# igvc-neopixel.net
KiCad netlist of a schematic drawn in EAGLE
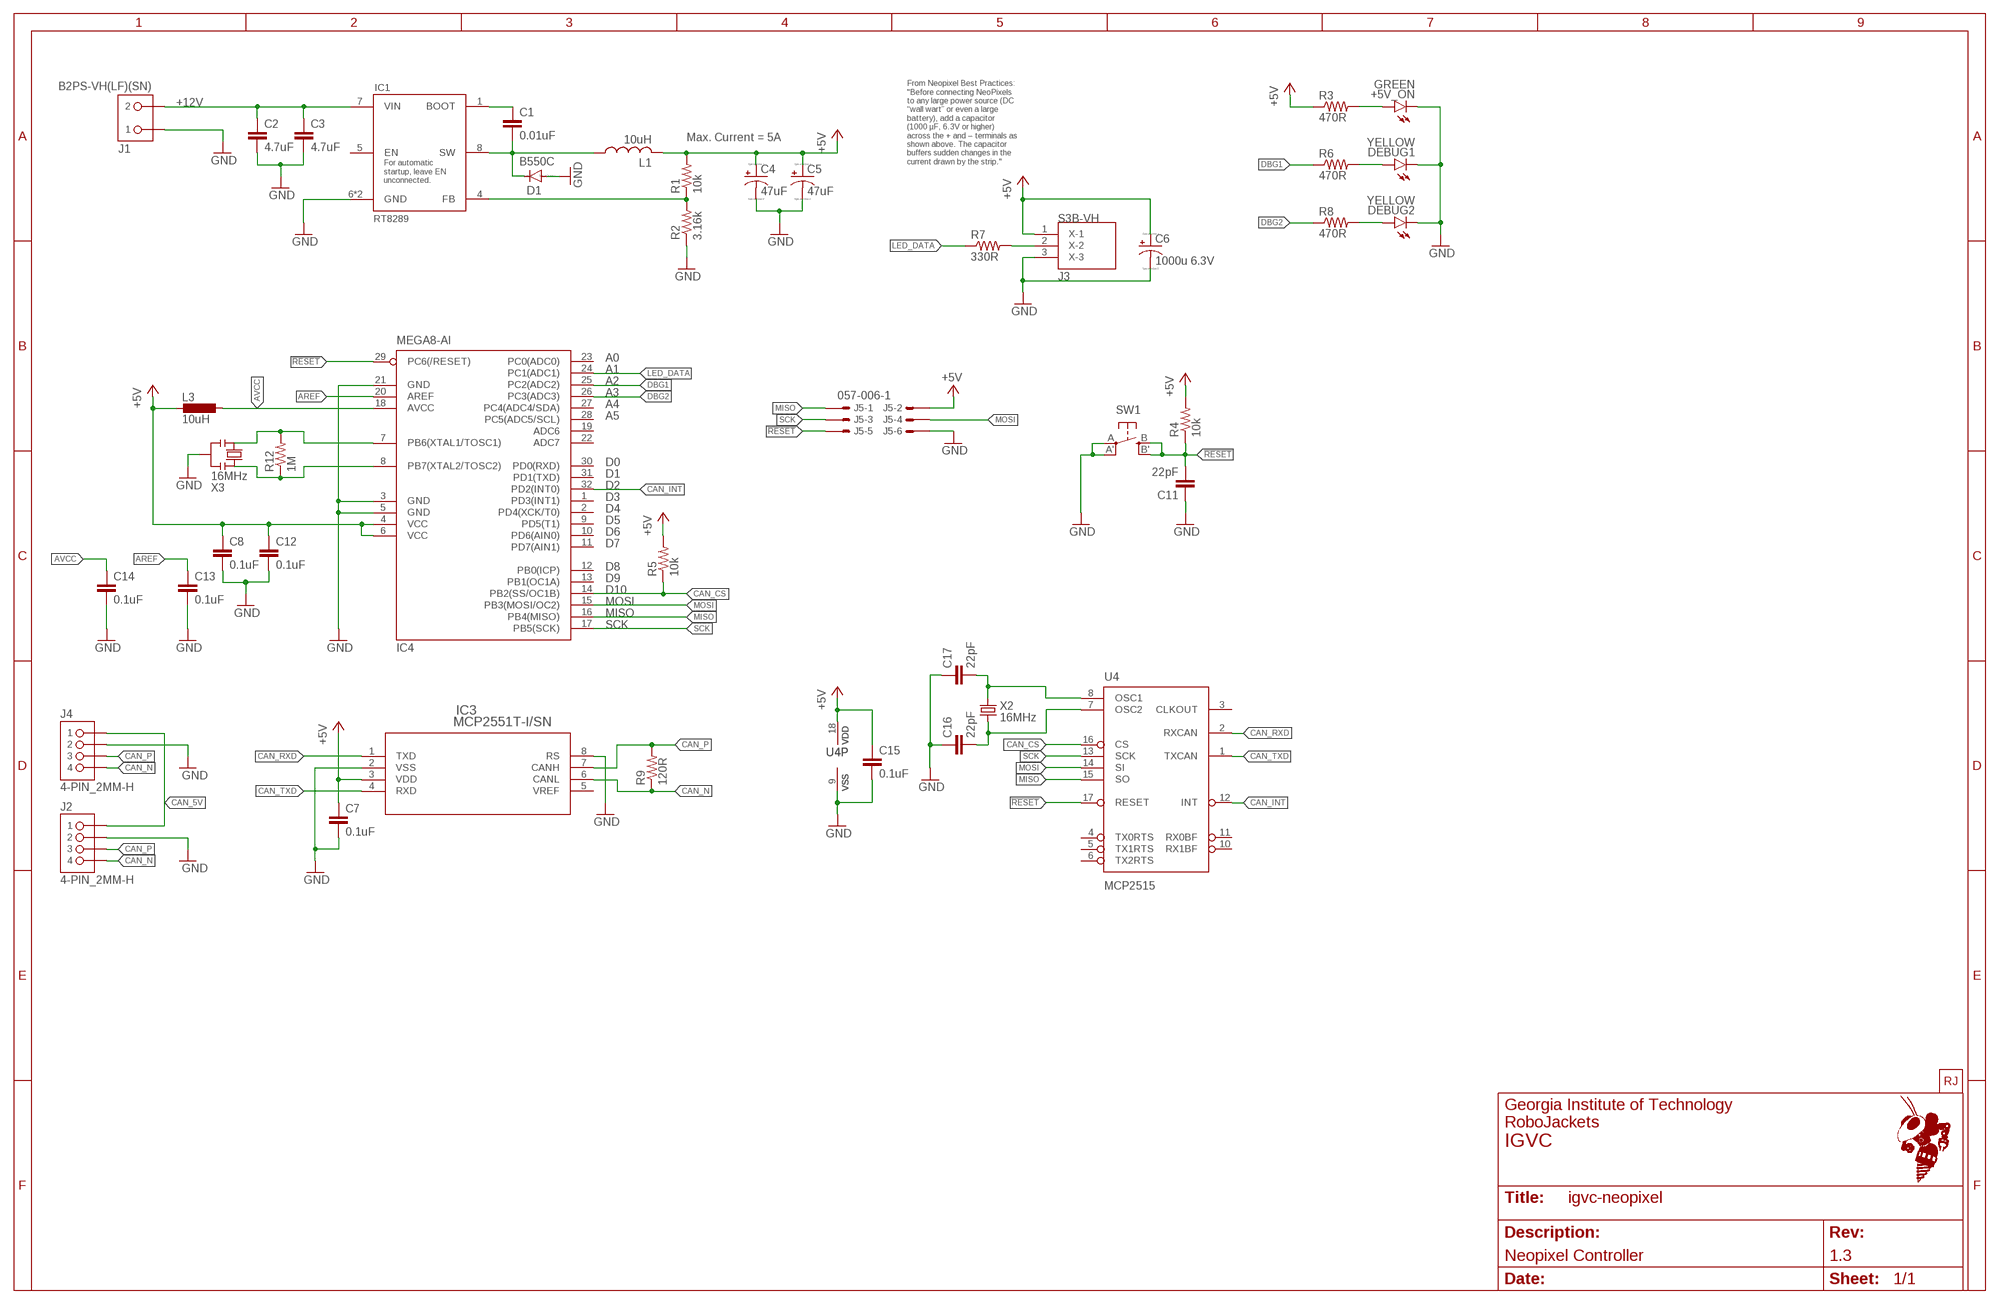
[diagram p0: schematic, sheet 1]

(export (version "E")
  (design (tool "Eeschema 10.0.6"))
  (components
    (comp (ref "+5V_ON")
      (value "GREEN")
      (footprint "eagle-import:CHIP-LED0805")
      (libsource (lib "eagle-import") (part "LEDCHIP-LED0805"))
    )
    (comp (ref "C1")
      (value "0.01uF")
      (footprint "eagle-import:C0603")
      (libsource (lib "eagle-import") (part "resistor_348_C-EUC0603"))
    )
    (comp (ref "C2")
      (value "4.7uF")
      (footprint "eagle-import:C1206")
      (libsource (lib "eagle-import") (part "resistor_348_C-EUC1206"))
    )
    (comp (ref "C3")
      (value "4.7uF")
      (footprint "eagle-import:C1206")
      (libsource (lib "eagle-import") (part "resistor_348_C-EUC1206"))
    )
    (comp (ref "C4")
      (value "47uF")
      (footprint "eagle-import:E5-10,5")
      (libsource (lib "eagle-import") (part "CPOL-USE5-10.5"))
    )
    (comp (ref "C5")
      (value "47uF")
      (footprint "eagle-import:E5-10,5")
      (libsource (lib "eagle-import") (part "CPOL-USE5-10.5"))
    )
    (comp (ref "C6")
      (value "1000u 6.3V")
      (footprint "eagle-import:E5-10,5")
      (libsource (lib "eagle-import") (part "CPOL-USE5-10.5"))
    )
    (comp (ref "C7")
      (value "0.1uF")
      (footprint "eagle-import:C0603")
      (libsource (lib "eagle-import") (part "C-EUC0603"))
    )
    (comp (ref "C8")
      (value "0.1uF")
      (footprint "eagle-import:C0603")
      (libsource (lib "eagle-import") (part "resistor_348_C-EUC0603"))
    )
    (comp (ref "C11")
      (value "22pF")
      (footprint "eagle-import:C0603")
      (libsource (lib "eagle-import") (part "resistor_348_C-EUC0603"))
    )
    (comp (ref "C12")
      (value "0.1uF")
      (footprint "eagle-import:C0603")
      (libsource (lib "eagle-import") (part "resistor_348_C-EUC0603"))
    )
    (comp (ref "C13")
      (value "0.1uF")
      (footprint "eagle-import:C0603")
      (libsource (lib "eagle-import") (part "resistor_348_C-EUC0603"))
    )
    (comp (ref "C14")
      (value "0.1uF")
      (footprint "eagle-import:C0603")
      (libsource (lib "eagle-import") (part "resistor_348_C-EUC0603"))
    )
    (comp (ref "C15")
      (value "0.1uF")
      (footprint "eagle-import:C0603")
      (libsource (lib "eagle-import") (part "C-EUC0603"))
    )
    (comp (ref "C16")
      (value "22pF")
      (footprint "eagle-import:C0603")
      (libsource (lib "eagle-import") (part "resistor_348_C-EUC0603"))
    )
    (comp (ref "C17")
      (value "22pF")
      (footprint "eagle-import:C0603")
      (libsource (lib "eagle-import") (part "resistor_348_C-EUC0603"))
    )
    (comp (ref "D1")
      (value "B550C")
      (footprint "eagle-import:SMC")
      (libsource (lib "eagle-import") (part "DIODE-SMC"))
    )
    (comp (ref "DEBUG1")
      (value "YELLOW")
      (footprint "eagle-import:CHIP-LED0805")
      (libsource (lib "eagle-import") (part "LEDCHIP-LED0805"))
    )
    (comp (ref "DEBUG2")
      (value "YELLOW")
      (footprint "eagle-import:CHIP-LED0805")
      (libsource (lib "eagle-import") (part "LEDCHIP-LED0805"))
    )
    (comp (ref "IC1")
      (value "RT8289")
      (footprint "eagle-import:SOIC8_EP")
      (libsource (lib "eagle-import") (part "RT8289"))
    )
    (comp (ref "IC3")
      (value "MCP2551T-I/SN")
      (footprint "eagle-import:SOIC8-N_MC")
      (fields (field (name "MANUFACTURER_PART_NUMBER") "MCP2551TISN"))
      (libsource (lib "eagle-import") (part "MCP2551T-I/SN"))
    )
    (comp (ref "IC4")
      (value "MEGA8-AI")
      (footprint "eagle-import:TQFP32-08")
      (fields (field (name "MPN") "ATMEGA8-16AU"))
      (libsource (lib "eagle-import") (part "MEGA8-AI"))
    )
    (comp (ref "J1")
      (value "B2PS-VH(LF)(SN)")
      (footprint "eagle-import:B2PS-CENTERED")
      (libsource (lib "eagle-import") (part "B2P?-VH(LF)(SN)S"))
    )
    (comp (ref "J2")
      (value "4-PIN_2MM-H")
      (footprint "eagle-import:2MM-4-H")
      (fields (field (name "MPN") "0353630460"))
      (libsource (lib "eagle-import") (part "4-PIN_2MM-H"))
    )
    (comp (ref "J3")
      (value "S3B-VH")
      (footprint "eagle-import:S3B-VH")
      (libsource (lib "eagle-import") (part "S3B-VH"))
    )
    (comp (ref "J4")
      (value "4-PIN_2MM-H")
      (footprint "eagle-import:2MM-4-H")
      (fields (field (name "MPN") "0353630460"))
      (libsource (lib "eagle-import") (part "4-PIN_2MM-H"))
    )
    (comp (ref "J5")
      (value "057-006-1")
      (footprint "eagle-import:057-006-1")
      (fields (field (name "DIGIKEY") "3M15451-ND"))
      (libsource (lib "eagle-import") (part "057-006-1"))
    )
    (comp (ref "L1")
      (value "10uH")
      (footprint "eagle-import:SRR1208")
      (libsource (lib "eagle-import") (part "SRR1208"))
    )
    (comp (ref "L3")
      (value "10uH")
      (footprint "eagle-import:0805")
      (libsource (lib "eagle-import") (part "L-0805"))
    )
    (comp (ref "R1")
      (value "10k")
      (footprint "eagle-import:R0603")
      (libsource (lib "eagle-import") (part "resistor_348_R-US_R0603"))
    )
    (comp (ref "R2")
      (value "3.16k")
      (footprint "eagle-import:R0603")
      (libsource (lib "eagle-import") (part "resistor_348_R-US_R0603"))
    )
    (comp (ref "R3")
      (value "470R")
      (footprint "eagle-import:R0603")
      (libsource (lib "eagle-import") (part "resistor_348_R-US_R0603"))
    )
    (comp (ref "R4")
      (value "10k")
      (footprint "eagle-import:R0603")
      (libsource (lib "eagle-import") (part "resistor_348_R-US_R0603"))
    )
    (comp (ref "R5")
      (value "10k")
      (footprint "eagle-import:R0603")
      (libsource (lib "eagle-import") (part "R-US_R0603"))
    )
    (comp (ref "R6")
      (value "470R")
      (footprint "eagle-import:R0603")
      (libsource (lib "eagle-import") (part "resistor_348_R-US_R0603"))
    )
    (comp (ref "R7")
      (value "330R")
      (footprint "eagle-import:R0603")
      (libsource (lib "eagle-import") (part "R-US_R0603"))
    )
    (comp (ref "R8")
      (value "470R")
      (footprint "eagle-import:R0603")
      (libsource (lib "eagle-import") (part "resistor_348_R-US_R0603"))
    )
    (comp (ref "R9")
      (value "120R")
      (footprint "eagle-import:R0603")
      (libsource (lib "eagle-import") (part "R-US_R0603"))
    )
    (comp (ref "R12")
      (value "1M")
      (footprint "eagle-import:R0603")
      (libsource (lib "eagle-import") (part "resistor_348_R-US_R0603"))
    )
    (comp (ref "SW1")
      (value "SPST_TACT-EVQQ2")
      (footprint "eagle-import:EVQ-Q2")
      (libsource (lib "eagle-import") (part "SPST_TACT-EVQQ2"))
    )
    (comp (ref "U$1")
      (value "ROBOBUZZ0.6X")
      (footprint "eagle-import:ROBOBUZZ_0.6X")
      (libsource (lib "eagle-import") (part "ROBOBUZZ0.6X"))
    )
    (comp (ref "U4")
      (value "MCP2515")
      (footprint "eagle-import:SO-18W")
      (libsource (lib "eagle-import") (part "MCP2510SO"))
    )
    (comp (ref "X2")
      (value "16MHz")
      (footprint "eagle-import:CRYSTAL-SMD-5X3")
      (libsource (lib "eagle-import") (part "CRYSTAL5X3"))
    )
    (comp (ref "X3")
      (value "16MHz")
      (footprint "eagle-import:RESONATOR")
      (fields (field (name "PART_NUMBER") "CSTCE16M0V53-R0"))
      (libsource (lib "eagle-import") (part "OSC_CSTCE16M0V53-R0"))
    )
  )
  (nets
    (net (code "1") (name "+5V") (class "Default")
      (node (ref "C12") (pin "1") (pinfunction "1_1") (pintype "passive"))
      (node (ref "C15") (pin "1") (pinfunction "1_1") (pintype "passive"))
      (node (ref "C4") (pin "+") (pinfunction "+_+") (pintype "passive"))
      (node (ref "C5") (pin "+") (pinfunction "+_+") (pintype "passive"))
      (node (ref "C6") (pin "+") (pinfunction "+_+") (pintype "passive"))
      (node (ref "C7") (pin "1") (pinfunction "1_1") (pintype "passive"))
      (node (ref "C8") (pin "1") (pinfunction "1_1") (pintype "passive"))
      (node (ref "IC3") (pin "3") (pinfunction "VDD_3") (pintype "passive"))
      (node (ref "IC4") (pin "4") (pinfunction "VCC_4") (pintype "power_in"))
      (node (ref "IC4") (pin "6") (pinfunction "VCC_6") (pintype "power_in"))
      (node (ref "J3") (pin "1") (pinfunction "X-1_1") (pintype "bidirectional"))
      (node (ref "J5") (pin "2") (pinfunction "S_2") (pintype "passive"))
      (node (ref "L1") (pin "2") (pinfunction "2_2") (pintype "passive"))
      (node (ref "L3") (pin "2") (pinfunction "2_2") (pintype "passive"))
      (node (ref "R1") (pin "2") (pinfunction "2_2") (pintype "passive"))
      (node (ref "R3") (pin "1") (pinfunction "1_1") (pintype "passive"))
      (node (ref "R4") (pin "2") (pinfunction "2_2") (pintype "passive"))
      (node (ref "R5") (pin "2") (pinfunction "2_2") (pintype "passive"))
      (node (ref "U4") (pin "18") (pinfunction "VDD_18") (pintype "power_in"))
    )
    (net (code "2") (name "/+12V") (class "Default")
      (node (ref "C2") (pin "1") (pinfunction "1_1") (pintype "passive"))
      (node (ref "C3") (pin "1") (pinfunction "1_1") (pintype "passive"))
      (node (ref "IC1") (pin "7") (pinfunction "VIN_7") (pintype "power_in"))
      (node (ref "J1") (pin "2") (pinfunction "2_2") (pintype "bidirectional"))
    )
    (net (code "3") (name "/~{RESET}") (class "Default")
      (node (ref "C11") (pin "2") (pinfunction "2_2") (pintype "passive"))
      (node (ref "IC4") (pin "29") (pinfunction "PC6(/RESET)_29") (pintype "bidirectional"))
      (node (ref "J5") (pin "5") (pinfunction "S_5") (pintype "passive"))
      (node (ref "R4") (pin "1") (pinfunction "1_1") (pintype "passive"))
      (node (ref "SW1") (pin "B") (pinfunction "S_B") (pintype "passive"))
      (node (ref "SW1") (pin "B'") (pinfunction "S1_B'") (pintype "passive"))
      (node (ref "U4") (pin "17") (pinfunction "RESET_17") (pintype "input"))
    )
    (net (code "4") (name "AREF") (class "Default")
      (node (ref "C13") (pin "1") (pinfunction "1_1") (pintype "passive"))
      (node (ref "IC4") (pin "20") (pinfunction "AREF_20") (pintype "passive"))
    )
    (net (code "5") (name "AVCC") (class "Default")
      (node (ref "C14") (pin "1") (pinfunction "1_1") (pintype "passive"))
      (node (ref "IC4") (pin "18") (pinfunction "AVCC_18") (pintype "power_in"))
      (node (ref "L3") (pin "1") (pinfunction "1_1") (pintype "passive"))
    )
    (net (code "6") (name "CAN_5V") (class "Default")
      (node (ref "J2") (pin "1") (pinfunction "1_1") (pintype "passive"))
      (node (ref "J4") (pin "1") (pinfunction "1_1") (pintype "passive"))
    )
    (net (code "7") (name "CAN_CS") (class "Default")
      (node (ref "IC4") (pin "14") (pinfunction "PB2(SS/OC1B)_14") (pintype "bidirectional"))
      (node (ref "R5") (pin "1") (pinfunction "1_1") (pintype "passive"))
      (node (ref "U4") (pin "16") (pinfunction "CS_16") (pintype "input"))
    )
    (net (code "8") (name "CAN_INT") (class "Default")
      (node (ref "IC4") (pin "32") (pinfunction "PD2(INT0)_32") (pintype "bidirectional"))
      (node (ref "U4") (pin "12") (pinfunction "INT_12") (pintype "output"))
    )
    (net (code "9") (name "CAN_N") (class "Default")
      (node (ref "IC3") (pin "6") (pinfunction "CANL_6") (pintype "passive"))
      (node (ref "J2") (pin "4") (pinfunction "4_4") (pintype "passive"))
      (node (ref "J4") (pin "4") (pinfunction "4_4") (pintype "passive"))
      (node (ref "R9") (pin "1") (pinfunction "1_1") (pintype "passive"))
    )
    (net (code "10") (name "CAN_P") (class "Default")
      (node (ref "IC3") (pin "7") (pinfunction "CANH_7") (pintype "passive"))
      (node (ref "J2") (pin "3") (pinfunction "3_3") (pintype "passive"))
      (node (ref "J4") (pin "3") (pinfunction "3_3") (pintype "passive"))
      (node (ref "R9") (pin "2") (pinfunction "2_2") (pintype "passive"))
    )
    (net (code "11") (name "CAN_RXD") (class "Default")
      (node (ref "IC3") (pin "1") (pinfunction "TXD_1") (pintype "passive"))
      (node (ref "U4") (pin "2") (pinfunction "RXCAN_2") (pintype "input"))
    )
    (net (code "12") (name "CAN_TXD") (class "Default")
      (node (ref "IC3") (pin "4") (pinfunction "RXD_4") (pintype "passive"))
      (node (ref "U4") (pin "1") (pinfunction "TXCAN_1") (pintype "output"))
    )
    (net (code "13") (name "DBG1") (class "Default")
      (node (ref "IC4") (pin "25") (pinfunction "PC2(ADC2)_25") (pintype "bidirectional"))
      (node (ref "R6") (pin "1") (pinfunction "1_1") (pintype "passive"))
    )
    (net (code "14") (name "DBG2") (class "Default")
      (node (ref "IC4") (pin "26") (pinfunction "PC3(ADC3)_26") (pintype "bidirectional"))
      (node (ref "R8") (pin "1") (pinfunction "1_1") (pintype "passive"))
    )
    (net (code "15") (name "GND") (class "Default")
      (node (ref "+5V_ON") (pin "C") (pinfunction "C_C") (pintype "passive"))
      (node (ref "C11") (pin "1") (pinfunction "1_1") (pintype "passive"))
      (node (ref "C12") (pin "2") (pinfunction "2_2") (pintype "passive"))
      (node (ref "C13") (pin "2") (pinfunction "2_2") (pintype "passive"))
      (node (ref "C14") (pin "2") (pinfunction "2_2") (pintype "passive"))
      (node (ref "C15") (pin "2") (pinfunction "2_2") (pintype "passive"))
      (node (ref "C16") (pin "1") (pinfunction "1_1") (pintype "passive"))
      (node (ref "C17") (pin "1") (pinfunction "1_1") (pintype "passive"))
      (node (ref "C2") (pin "2") (pinfunction "2_2") (pintype "passive"))
      (node (ref "C3") (pin "2") (pinfunction "2_2") (pintype "passive"))
      (node (ref "C4") (pin "-") (pinfunction "-_-") (pintype "passive"))
      (node (ref "C5") (pin "-") (pinfunction "-_-") (pintype "passive"))
      (node (ref "C6") (pin "-") (pinfunction "-_-") (pintype "passive"))
      (node (ref "C7") (pin "2") (pinfunction "2_2") (pintype "passive"))
      (node (ref "C8") (pin "2") (pinfunction "2_2") (pintype "passive"))
      (node (ref "D1") (pin "A") (pinfunction "A_A") (pintype "passive"))
      (node (ref "DEBUG1") (pin "C") (pinfunction "C_C") (pintype "passive"))
      (node (ref "DEBUG2") (pin "C") (pinfunction "C_C") (pintype "passive"))
      (node (ref "IC1") (pin "6") (pinfunction "GND_6") (pintype "power_in"))
      (node (ref "IC1") (pin "EXP") (pinfunction "GND_EXP") (pintype "power_in"))
      (node (ref "IC3") (pin "2") (pinfunction "VSS_2") (pintype "passive"))
      (node (ref "IC3") (pin "8") (pinfunction "RS_8") (pintype "passive"))
      (node (ref "IC4") (pin "21") (pinfunction "GND_21") (pintype "power_in"))
      (node (ref "IC4") (pin "3") (pinfunction "GND_3") (pintype "power_in"))
      (node (ref "IC4") (pin "5") (pinfunction "GND_5") (pintype "power_in"))
      (node (ref "J1") (pin "1") (pinfunction "1_1") (pintype "bidirectional"))
      (node (ref "J2") (pin "2") (pinfunction "2_2") (pintype "passive"))
      (node (ref "J3") (pin "3") (pinfunction "X-3_3") (pintype "bidirectional"))
      (node (ref "J4") (pin "2") (pinfunction "2_2") (pintype "passive"))
      (node (ref "J5") (pin "6") (pinfunction "S_6") (pintype "passive"))
      (node (ref "R2") (pin "1") (pinfunction "1_1") (pintype "passive"))
      (node (ref "SW1") (pin "A") (pinfunction "P_A") (pintype "passive"))
      (node (ref "SW1") (pin "A'") (pinfunction "P1_A'") (pintype "passive"))
      (node (ref "U4") (pin "9") (pinfunction "VSS_9") (pintype "power_in"))
      (node (ref "X3") (pin "2") (pinfunction "2_2") (pintype "passive"))
    )
    (net (code "16") (name "LED_DATA") (class "Default")
      (node (ref "IC4") (pin "24") (pinfunction "PC1(ADC1)_24") (pintype "bidirectional"))
      (node (ref "R7") (pin "1") (pinfunction "1_1") (pintype "passive"))
    )
    (net (code "17") (name "MISO") (class "Default")
      (node (ref "IC4") (pin "16") (pinfunction "PB4(MISO)_16") (pintype "bidirectional"))
      (node (ref "J5") (pin "1") (pinfunction "S_1") (pintype "passive"))
      (node (ref "U4") (pin "15") (pinfunction "SO_15") (pintype "output"))
    )
    (net (code "18") (name "MOSI") (class "Default")
      (node (ref "IC4") (pin "15") (pinfunction "PB3(MOSI/OC2)_15") (pintype "bidirectional"))
      (node (ref "J5") (pin "4") (pinfunction "S_4") (pintype "passive"))
      (node (ref "U4") (pin "14") (pinfunction "SI_14") (pintype "input"))
    )
    (net (code "19") (name "Net-(+5V_ON-PadA)") (class "Default")
      (node (ref "+5V_ON") (pin "A") (pinfunction "A_A") (pintype "passive"))
      (node (ref "R3") (pin "2") (pinfunction "2_2") (pintype "passive"))
    )
    (net (code "20") (name "Net-(DEBUG1-PadA)") (class "Default")
      (node (ref "DEBUG1") (pin "A") (pinfunction "A_A") (pintype "passive"))
      (node (ref "R6") (pin "2") (pinfunction "2_2") (pintype "passive"))
    )
    (net (code "21") (name "Net-(DEBUG2-PadA)") (class "Default")
      (node (ref "DEBUG2") (pin "A") (pinfunction "A_A") (pintype "passive"))
      (node (ref "R8") (pin "2") (pinfunction "2_2") (pintype "passive"))
    )
    (net (code "22") (name "Net-(IC1-BOOT)") (class "Default")
      (node (ref "C1") (pin "1") (pinfunction "1_1") (pintype "passive"))
      (node (ref "IC1") (pin "1") (pinfunction "BOOT_1") (pintype "bidirectional"))
    )
    (net (code "23") (name "Net-(IC1-FB)") (class "Default")
      (node (ref "IC1") (pin "4") (pinfunction "FB_4") (pintype "bidirectional"))
      (node (ref "R1") (pin "1") (pinfunction "1_1") (pintype "passive"))
      (node (ref "R2") (pin "2") (pinfunction "2_2") (pintype "passive"))
    )
    (net (code "24") (name "Net-(IC1-SW)") (class "Default")
      (node (ref "C1") (pin "2") (pinfunction "2_2") (pintype "passive"))
      (node (ref "D1") (pin "C") (pinfunction "C_C") (pintype "passive"))
      (node (ref "IC1") (pin "8") (pinfunction "SW_8") (pintype "power_in"))
      (node (ref "L1") (pin "1") (pinfunction "1_1") (pintype "passive"))
    )
    (net (code "25") (name "Net-(IC4-PB6(XTAL1{slash}TOSC1))") (class "Default")
      (node (ref "IC4") (pin "7") (pinfunction "PB6(XTAL1/TOSC1)_7") (pintype "bidirectional"))
      (node (ref "R12") (pin "2") (pinfunction "2_2") (pintype "passive"))
      (node (ref "X3") (pin "1") (pinfunction "1_1") (pintype "passive"))
    )
    (net (code "26") (name "Net-(IC4-PB7(XTAL2{slash}TOSC2))") (class "Default")
      (node (ref "IC4") (pin "8") (pinfunction "PB7(XTAL2/TOSC2)_8") (pintype "bidirectional"))
      (node (ref "R12") (pin "1") (pinfunction "1_1") (pintype "passive"))
      (node (ref "X3") (pin "3") (pinfunction "3_3") (pintype "passive"))
    )
    (net (code "27") (name "Net-(J3-X-2)") (class "Default")
      (node (ref "J3") (pin "2") (pinfunction "X-2_2") (pintype "bidirectional"))
      (node (ref "R7") (pin "2") (pinfunction "2_2") (pintype "passive"))
    )
    (net (code "28") (name "Net-(U4A-OSC1)") (class "Default")
      (node (ref "C17") (pin "2") (pinfunction "2_2") (pintype "passive"))
      (node (ref "U4") (pin "8") (pinfunction "OSC1_8") (pintype "input"))
      (node (ref "X2") (pin "3") (pinfunction "2_3") (pintype "passive"))
    )
    (net (code "29") (name "Net-(U4A-OSC2)") (class "Default")
      (node (ref "C16") (pin "2") (pinfunction "2_2") (pintype "passive"))
      (node (ref "U4") (pin "7") (pinfunction "OSC2_7") (pintype "output"))
      (node (ref "X2") (pin "1") (pinfunction "1_1") (pintype "passive"))
    )
    (net (code "30") (name "SCK") (class "Default")
      (node (ref "IC4") (pin "17") (pinfunction "PB5(SCK)_17") (pintype "bidirectional"))
      (node (ref "J5") (pin "3") (pinfunction "S_3") (pintype "passive"))
      (node (ref "U4") (pin "13") (pinfunction "SCK_13") (pintype "input"))
    )
    (net (code "31") (name "unconnected-(IC1-EN-Pad5)") (class "Default")
      (node (ref "IC1") (pin "5") (pinfunction "EN_5") (pintype "bidirectional"))
    )
    (net (code "32") (name "unconnected-(IC3-VREF-Pad5)") (class "Default")
      (node (ref "IC3") (pin "5") (pinfunction "VREF_5") (pintype "passive"))
    )
    (net (code "33") (name "unconnected-(IC4-ADC6-Pad19)") (class "Default")
      (node (ref "IC4") (pin "19") (pinfunction "ADC6_19") (pintype "bidirectional"))
    )
    (net (code "34") (name "unconnected-(IC4-ADC7-Pad22)") (class "Default")
      (node (ref "IC4") (pin "22") (pinfunction "ADC7_22") (pintype "bidirectional"))
    )
    (net (code "35") (name "unconnected-(IC4-PB0(ICP)-Pad12)") (class "Default")
      (node (ref "IC4") (pin "12") (pinfunction "PB0(ICP)_12") (pintype "bidirectional"))
    )
    (net (code "36") (name "unconnected-(IC4-PB1(OC1A)-Pad13)") (class "Default")
      (node (ref "IC4") (pin "13") (pinfunction "PB1(OC1A)_13") (pintype "bidirectional"))
    )
    (net (code "37") (name "unconnected-(IC4-PC0(ADC0)-Pad23)") (class "Default")
      (node (ref "IC4") (pin "23") (pinfunction "PC0(ADC0)_23") (pintype "bidirectional"))
    )
    (net (code "38") (name "unconnected-(IC4-PC4(ADC4{slash}SDA)-Pad27)") (class "Default")
      (node (ref "IC4") (pin "27") (pinfunction "PC4(ADC4/SDA)_27") (pintype "bidirectional"))
    )
    (net (code "39") (name "unconnected-(IC4-PC5(ADC5{slash}SCL)-Pad28)") (class "Default")
      (node (ref "IC4") (pin "28") (pinfunction "PC5(ADC5/SCL)_28") (pintype "bidirectional"))
    )
    (net (code "40") (name "unconnected-(IC4-PD0(RXD)-Pad30)") (class "Default")
      (node (ref "IC4") (pin "30") (pinfunction "PD0(RXD)_30") (pintype "bidirectional"))
    )
    (net (code "41") (name "unconnected-(IC4-PD1(TXD)-Pad31)") (class "Default")
      (node (ref "IC4") (pin "31") (pinfunction "PD1(TXD)_31") (pintype "bidirectional"))
    )
    (net (code "42") (name "unconnected-(IC4-PD3(INT1)-Pad1)") (class "Default")
      (node (ref "IC4") (pin "1") (pinfunction "PD3(INT1)_1") (pintype "bidirectional"))
    )
    (net (code "43") (name "unconnected-(IC4-PD4(XCK{slash}T0)-Pad2)") (class "Default")
      (node (ref "IC4") (pin "2") (pinfunction "PD4(XCK/T0)_2") (pintype "bidirectional"))
    )
    (net (code "44") (name "unconnected-(IC4-PD5(T1)-Pad9)") (class "Default")
      (node (ref "IC4") (pin "9") (pinfunction "PD5(T1)_9") (pintype "bidirectional"))
    )
    (net (code "45") (name "unconnected-(IC4-PD6(AIN0)-Pad10)") (class "Default")
      (node (ref "IC4") (pin "10") (pinfunction "PD6(AIN0)_10") (pintype "bidirectional"))
    )
    (net (code "46") (name "unconnected-(IC4-PD7(AIN1)-Pad11)") (class "Default")
      (node (ref "IC4") (pin "11") (pinfunction "PD7(AIN1)_11") (pintype "bidirectional"))
    )
    (net (code "47") (name "unconnected-(U4A-CLKOUT-Pad3)") (class "Default")
      (node (ref "U4") (pin "3") (pinfunction "CLKOUT_3") (pintype "output"))
    )
    (net (code "48") (name "unconnected-(U4A-RX0BF-Pad11)") (class "Default")
      (node (ref "U4") (pin "11") (pinfunction "RX0BF_11") (pintype "output"))
    )
    (net (code "49") (name "unconnected-(U4A-RX1BF-Pad10)") (class "Default")
      (node (ref "U4") (pin "10") (pinfunction "RX1BF_10") (pintype "output"))
    )
    (net (code "50") (name "unconnected-(U4A-TX0RTS-Pad4)") (class "Default")
      (node (ref "U4") (pin "4") (pinfunction "TX0RTS_4") (pintype "input"))
    )
    (net (code "51") (name "unconnected-(U4A-TX1RTS-Pad5)") (class "Default")
      (node (ref "U4") (pin "5") (pinfunction "TX1RTS_5") (pintype "input"))
    )
    (net (code "52") (name "unconnected-(U4A-TX2RTS-Pad6)") (class "Default")
      (node (ref "U4") (pin "6") (pinfunction "TX2RTS_6") (pintype "input"))
    )
  )
)
